# megaRF-mini-2_4_1.net
KiCad netlist of a schematic drawn in EAGLE
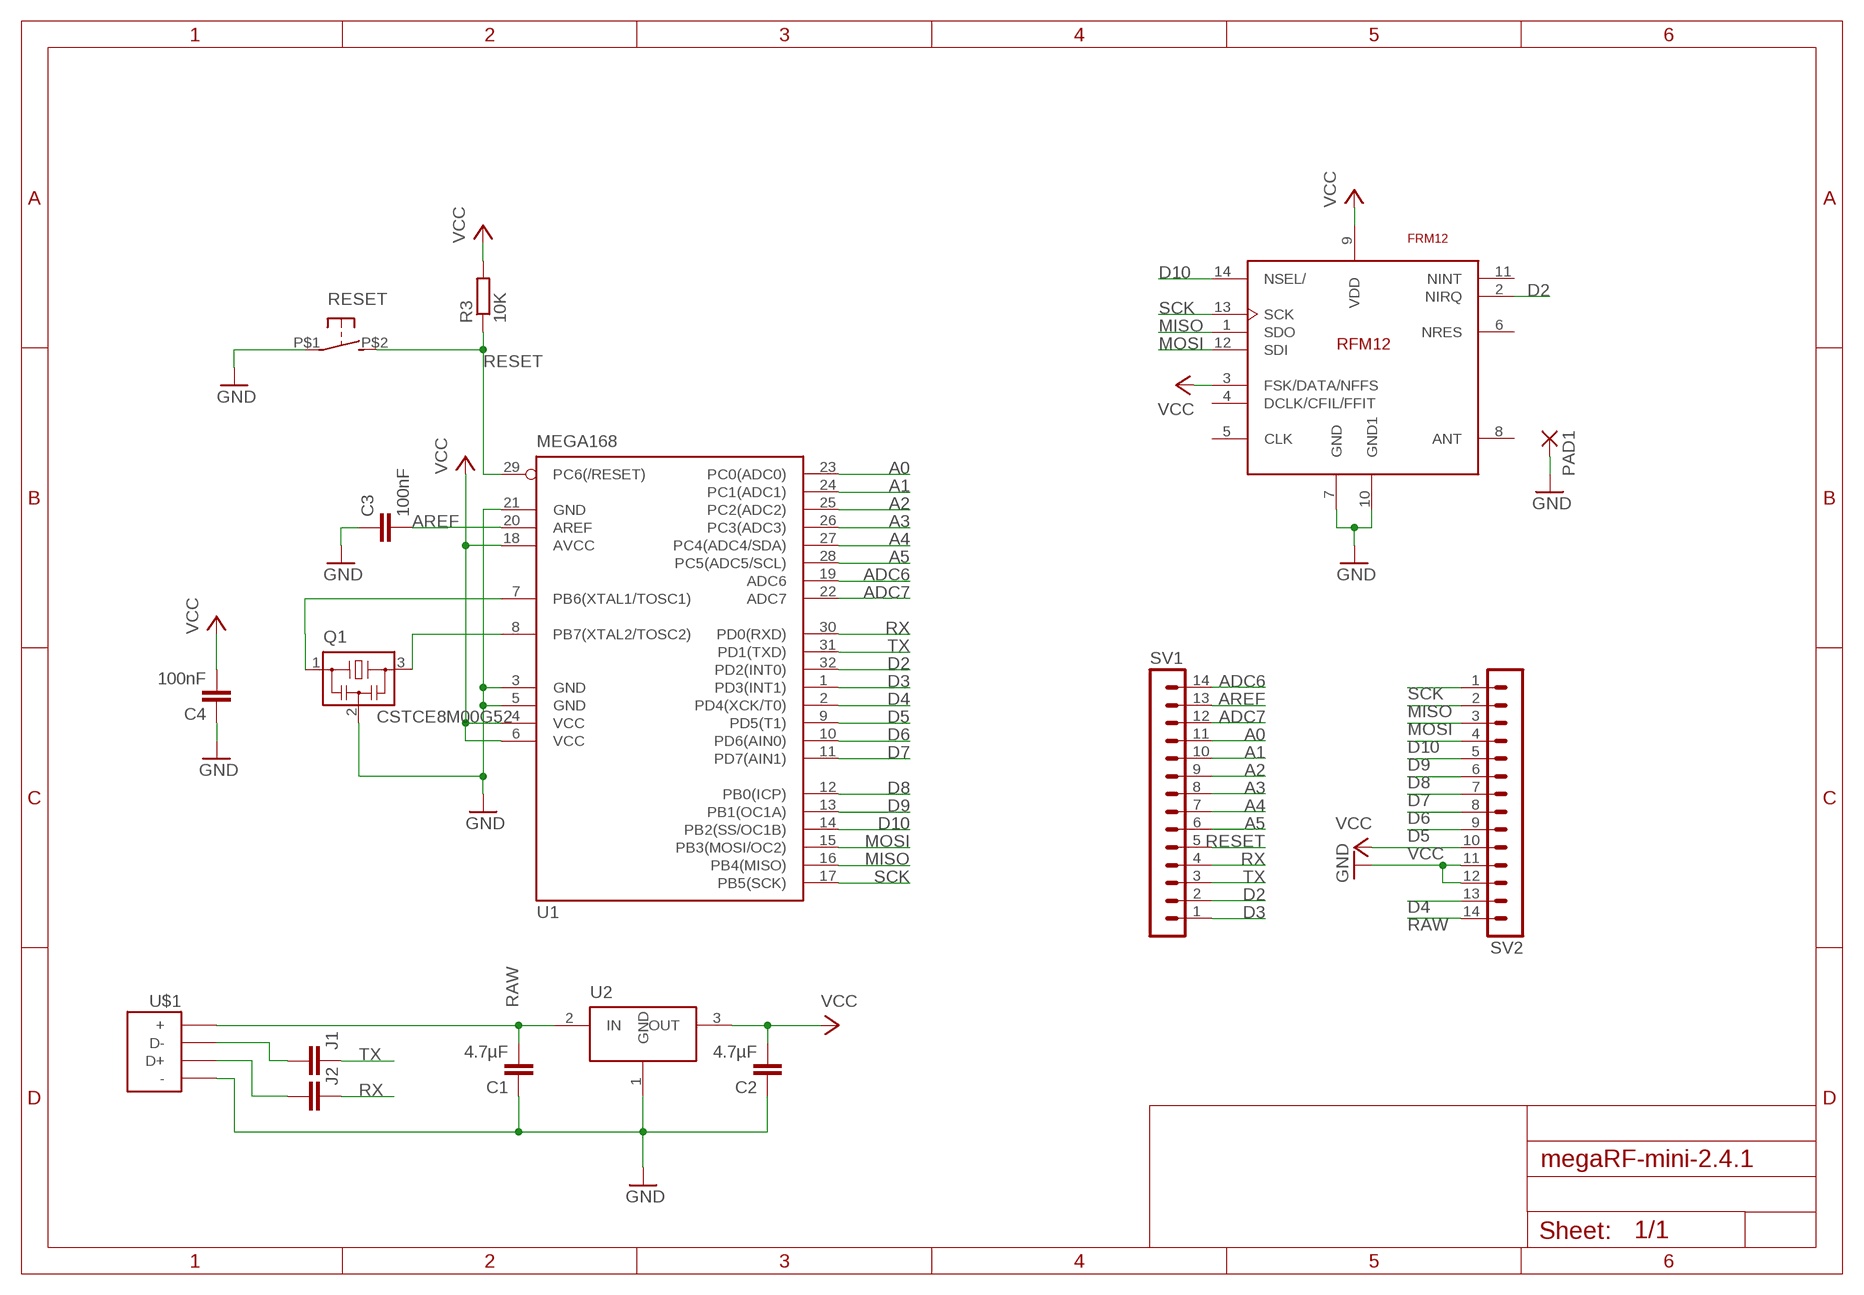
[diagram p0: schematic, sheet 1]

(export (version "E")
  (design (tool "Eeschema 10.0.6"))
  (components
    (comp (ref "C1")
      (value "4.7µF")
      (footprint "eagle-import:C0805")
      (libsource (lib "eagle-import") (part "C-EUC0805"))
    )
    (comp (ref "C2")
      (value "4.7µF")
      (footprint "eagle-import:C0805")
      (libsource (lib "eagle-import") (part "C-EUC0805"))
    )
    (comp (ref "C3")
      (value "100nF")
      (footprint "eagle-import:C0603K")
      (libsource (lib "eagle-import") (part "C-EUC0603K"))
    )
    (comp (ref "C4")
      (value "100nF")
      (footprint "eagle-import:C0603K")
      (libsource (lib "eagle-import") (part "C-EUC0603K"))
    )
    (comp (ref "J1")
      (value "C-EUC0402")
      (footprint "eagle-import:C0402")
      (libsource (lib "eagle-import") (part "C-EUC0402"))
    )
    (comp (ref "J2")
      (value "C-EUC0402")
      (footprint "eagle-import:C0402")
      (libsource (lib "eagle-import") (part "C-EUC0402"))
    )
    (comp (ref "PAD1")
      (value "SMD2")
      (footprint "eagle-import:SMD1,27-2,54")
      (libsource (lib "eagle-import") (part "SMD2"))
    )
    (comp (ref "Q1")
      (value "CSTCE8M00G52")
      (footprint "eagle-import:CSTCE8M00G52")
      (libsource (lib "eagle-import") (part "CSTCE8M00G52"))
    )
    (comp (ref "R3")
      (value "10K")
      (footprint "eagle-import:R0603")
      (libsource (lib "eagle-import") (part "R-EU_R0603"))
    )
    (comp (ref "RESET")
      (value "DTSM-3")
      (footprint "eagle-import:DTSM31N")
      (libsource (lib "eagle-import") (part "DTSM-3"))
    )
    (comp (ref "RFM12")
      (value "FRM12")
      (footprint "eagle-import:RFM12")
      (libsource (lib "eagle-import") (part "FRM12"))
    )
    (comp (ref "SV1")
      (value "MA14-1")
      (footprint "eagle-import:MA14-1")
      (libsource (lib "eagle-import") (part "MA14-1"))
    )
    (comp (ref "SV2")
      (value "MA14-1")
      (footprint "eagle-import:MA14-1")
      (libsource (lib "eagle-import") (part "MA14-1"))
    )
    (comp (ref "U$1")
      (value "USB-MICRO-B-RS")
      (footprint "eagle-import:USB-MICRO-B-RS")
      (libsource (lib "eagle-import") (part "USB-MICRO-B-RS"))
    )
    (comp (ref "U1")
      (value "MEGA168")
      (footprint "eagle-import:TQFP32-08")
      (fields (field (name "MPN") "ATMEGA8-16AU"))
      (libsource (lib "eagle-import") (part "MEGA8-AI"))
    )
    (comp (ref "U2")
      (value "TS1117CP33")
      (footprint "eagle-import:TO252")
      (libsource (lib "eagle-import") (part "TS1117CP33"))
    )
  )
  (nets
    (net (code "1") (name "/A0") (class "Default")
      (node (ref "SV1") (pin "11") (pinfunction "11_11") (pintype "passive"))
      (node (ref "U1") (pin "23") (pinfunction "PC0(ADC0)_23") (pintype "bidirectional"))
    )
    (net (code "2") (name "/A1") (class "Default")
      (node (ref "SV1") (pin "10") (pinfunction "10_10") (pintype "passive"))
      (node (ref "U1") (pin "24") (pinfunction "PC1(ADC1)_24") (pintype "bidirectional"))
    )
    (net (code "3") (name "/A2") (class "Default")
      (node (ref "SV1") (pin "9") (pinfunction "9_9") (pintype "passive"))
      (node (ref "U1") (pin "25") (pinfunction "PC2(ADC2)_25") (pintype "bidirectional"))
    )
    (net (code "4") (name "/A3") (class "Default")
      (node (ref "SV1") (pin "8") (pinfunction "8_8") (pintype "passive"))
      (node (ref "U1") (pin "26") (pinfunction "PC3(ADC3)_26") (pintype "bidirectional"))
    )
    (net (code "5") (name "/A4") (class "Default")
      (node (ref "SV1") (pin "7") (pinfunction "7_7") (pintype "passive"))
      (node (ref "U1") (pin "27") (pinfunction "PC4(ADC4/SDA)_27") (pintype "bidirectional"))
    )
    (net (code "6") (name "/A5") (class "Default")
      (node (ref "SV1") (pin "6") (pinfunction "6_6") (pintype "passive"))
      (node (ref "U1") (pin "28") (pinfunction "PC5(ADC5/SCL)_28") (pintype "bidirectional"))
    )
    (net (code "7") (name "/ADC6") (class "Default")
      (node (ref "SV1") (pin "14") (pinfunction "14_14") (pintype "passive"))
      (node (ref "U1") (pin "19") (pinfunction "ADC6_19") (pintype "bidirectional"))
    )
    (net (code "8") (name "/ADC7") (class "Default")
      (node (ref "SV1") (pin "12") (pinfunction "12_12") (pintype "passive"))
      (node (ref "U1") (pin "22") (pinfunction "ADC7_22") (pintype "bidirectional"))
    )
    (net (code "9") (name "/AREF") (class "Default")
      (node (ref "C3") (pin "2") (pinfunction "2_2") (pintype "passive"))
      (node (ref "SV1") (pin "13") (pinfunction "13_13") (pintype "passive"))
      (node (ref "U1") (pin "20") (pinfunction "AREF_20") (pintype "passive"))
    )
    (net (code "10") (name "/D2") (class "Default")
      (node (ref "RFM12") (pin "2") (pinfunction "NIRQ_2") (pintype "output"))
      (node (ref "SV1") (pin "2") (pinfunction "2_2") (pintype "passive"))
      (node (ref "U1") (pin "32") (pinfunction "PD2(INT0)_32") (pintype "bidirectional"))
    )
    (net (code "11") (name "/D3") (class "Default")
      (node (ref "SV1") (pin "1") (pinfunction "1_1") (pintype "passive"))
      (node (ref "U1") (pin "1") (pinfunction "PD3(INT1)_1") (pintype "bidirectional"))
    )
    (net (code "12") (name "/D4") (class "Default")
      (node (ref "SV2") (pin "13") (pinfunction "13_13") (pintype "passive"))
      (node (ref "U1") (pin "2") (pinfunction "PD4(XCK/T0)_2") (pintype "bidirectional"))
    )
    (net (code "13") (name "/D5") (class "Default")
      (node (ref "SV2") (pin "9") (pinfunction "9_9") (pintype "passive"))
      (node (ref "U1") (pin "9") (pinfunction "PD5(T1)_9") (pintype "bidirectional"))
    )
    (net (code "14") (name "/D6") (class "Default")
      (node (ref "SV2") (pin "8") (pinfunction "8_8") (pintype "passive"))
      (node (ref "U1") (pin "10") (pinfunction "PD6(AIN0)_10") (pintype "bidirectional"))
    )
    (net (code "15") (name "/D7") (class "Default")
      (node (ref "SV2") (pin "7") (pinfunction "7_7") (pintype "passive"))
      (node (ref "U1") (pin "11") (pinfunction "PD7(AIN1)_11") (pintype "bidirectional"))
    )
    (net (code "16") (name "/D8") (class "Default")
      (node (ref "SV2") (pin "6") (pinfunction "6_6") (pintype "passive"))
      (node (ref "U1") (pin "12") (pinfunction "PB0(ICP)_12") (pintype "bidirectional"))
    )
    (net (code "17") (name "/D9") (class "Default")
      (node (ref "SV2") (pin "5") (pinfunction "5_5") (pintype "passive"))
      (node (ref "U1") (pin "13") (pinfunction "PB1(OC1A)_13") (pintype "bidirectional"))
    )
    (net (code "18") (name "/D10") (class "Default")
      (node (ref "RFM12") (pin "14") (pinfunction "NSEL/_14") (pintype "input"))
      (node (ref "SV2") (pin "4") (pinfunction "4_4") (pintype "passive"))
      (node (ref "U1") (pin "14") (pinfunction "PB2(SS/OC1B)_14") (pintype "bidirectional"))
    )
    (net (code "19") (name "/MISO") (class "Default")
      (node (ref "RFM12") (pin "1") (pinfunction "SDO_1") (pintype "output"))
      (node (ref "SV2") (pin "2") (pinfunction "2_2") (pintype "passive"))
      (node (ref "U1") (pin "16") (pinfunction "PB4(MISO)_16") (pintype "bidirectional"))
    )
    (net (code "20") (name "/MOSI") (class "Default")
      (node (ref "RFM12") (pin "12") (pinfunction "SDI_12") (pintype "input"))
      (node (ref "SV2") (pin "3") (pinfunction "3_3") (pintype "passive"))
      (node (ref "U1") (pin "15") (pinfunction "PB3(MOSI/OC2)_15") (pintype "bidirectional"))
    )
    (net (code "21") (name "/RAW") (class "Default")
      (node (ref "C1") (pin "2") (pinfunction "2_2") (pintype "passive"))
      (node (ref "SV2") (pin "14") (pinfunction "14_14") (pintype "passive"))
      (node (ref "U$1") (pin "P$1") (pinfunction "+_P$1") (pintype "bidirectional"))
      (node (ref "U2") (pin "2") (pinfunction "IN_2") (pintype "bidirectional"))
    )
    (net (code "22") (name "/RESET") (class "Default")
      (node (ref "R3") (pin "1") (pinfunction "1_1") (pintype "passive"))
      (node (ref "RESET") (pin "P$2") (pinfunction "S_P$2") (pintype "passive"))
      (node (ref "SV1") (pin "5") (pinfunction "5_5") (pintype "passive"))
      (node (ref "U1") (pin "29") (pinfunction "PC6(/RESET)_29") (pintype "bidirectional"))
    )
    (net (code "23") (name "/RX") (class "Default")
      (node (ref "J2") (pin "2") (pinfunction "2_2") (pintype "passive"))
      (node (ref "SV1") (pin "4") (pinfunction "4_4") (pintype "passive"))
      (node (ref "U1") (pin "30") (pinfunction "PD0(RXD)_30") (pintype "bidirectional"))
    )
    (net (code "24") (name "/SCK") (class "Default")
      (node (ref "RFM12") (pin "13") (pinfunction "SCK_13") (pintype "input"))
      (node (ref "SV2") (pin "1") (pinfunction "1_1") (pintype "passive"))
      (node (ref "U1") (pin "17") (pinfunction "PB5(SCK)_17") (pintype "bidirectional"))
    )
    (net (code "25") (name "/TX") (class "Default")
      (node (ref "J1") (pin "1") (pinfunction "1_1") (pintype "passive"))
      (node (ref "SV1") (pin "3") (pinfunction "3_3") (pintype "passive"))
      (node (ref "U1") (pin "31") (pinfunction "PD1(TXD)_31") (pintype "bidirectional"))
    )
    (net (code "26") (name "GND") (class "Default")
      (node (ref "C1") (pin "1") (pinfunction "1_1") (pintype "passive"))
      (node (ref "C2") (pin "1") (pinfunction "1_1") (pintype "passive"))
      (node (ref "C3") (pin "1") (pinfunction "1_1") (pintype "passive"))
      (node (ref "C4") (pin "1") (pinfunction "1_1") (pintype "passive"))
      (node (ref "PAD1") (pin "1") (pinfunction "P_1") (pintype "passive"))
      (node (ref "Q1") (pin "2") (pinfunction "2_2") (pintype "passive"))
      (node (ref "RESET") (pin "P$1") (pinfunction "P_P$1") (pintype "passive"))
      (node (ref "RFM12") (pin "10") (pinfunction "GND1_10") (pintype "passive"))
      (node (ref "RFM12") (pin "7") (pinfunction "GND_7") (pintype "passive"))
      (node (ref "SV2") (pin "11") (pinfunction "11_11") (pintype "passive"))
      (node (ref "SV2") (pin "12") (pinfunction "12_12") (pintype "passive"))
      (node (ref "U$1") (pin "P$5") (pinfunction "-_P$5") (pintype "bidirectional"))
      (node (ref "U1") (pin "21") (pinfunction "GND_21") (pintype "power_in"))
      (node (ref "U1") (pin "3") (pinfunction "GND_3") (pintype "power_in"))
      (node (ref "U1") (pin "5") (pinfunction "GND_5") (pintype "power_in"))
      (node (ref "U2") (pin "1") (pinfunction "GND_1") (pintype "bidirectional"))
    )
    (net (code "27") (name "Net-(U$1-D+)") (class "Default")
      (node (ref "J2") (pin "1") (pinfunction "1_1") (pintype "passive"))
      (node (ref "U$1") (pin "P$3") (pinfunction "D+_P$3") (pintype "bidirectional"))
    )
    (net (code "28") (name "Net-(U$1-D-)") (class "Default")
      (node (ref "J1") (pin "2") (pinfunction "2_2") (pintype "passive"))
      (node (ref "U$1") (pin "P$2") (pinfunction "D-_P$2") (pintype "bidirectional"))
    )
    (net (code "29") (name "Net-(U1-PB6(XTAL1{slash}TOSC1))") (class "Default")
      (node (ref "Q1") (pin "1") (pinfunction "1_1") (pintype "passive"))
      (node (ref "U1") (pin "7") (pinfunction "PB6(XTAL1/TOSC1)_7") (pintype "bidirectional"))
    )
    (net (code "30") (name "Net-(U1-PB7(XTAL2{slash}TOSC2))") (class "Default")
      (node (ref "Q1") (pin "3") (pinfunction "3_3") (pintype "passive"))
      (node (ref "U1") (pin "8") (pinfunction "PB7(XTAL2/TOSC2)_8") (pintype "bidirectional"))
    )
    (net (code "31") (name "VCC") (class "Default")
      (node (ref "C2") (pin "2") (pinfunction "2_2") (pintype "passive"))
      (node (ref "C4") (pin "2") (pinfunction "2_2") (pintype "passive"))
      (node (ref "R3") (pin "2") (pinfunction "2_2") (pintype "passive"))
      (node (ref "RFM12") (pin "3") (pinfunction "FSK/DATA/NFFS_3") (pintype "bidirectional"))
      (node (ref "RFM12") (pin "9") (pinfunction "VDD_9") (pintype "power_in"))
      (node (ref "SV2") (pin "10") (pinfunction "10_10") (pintype "passive"))
      (node (ref "U1") (pin "18") (pinfunction "AVCC_18") (pintype "power_in"))
      (node (ref "U1") (pin "4") (pinfunction "VCC_4") (pintype "power_in"))
      (node (ref "U1") (pin "6") (pinfunction "VCC_6") (pintype "power_in"))
      (node (ref "U2") (pin "3") (pinfunction "OUT_3") (pintype "bidirectional"))
    )
    (net (code "32") (name "unconnected-(RFM12-ANT-Pad8)") (class "Default")
      (node (ref "RFM12") (pin "8") (pinfunction "ANT_8") (pintype "bidirectional"))
    )
    (net (code "33") (name "unconnected-(RFM12-CLK-Pad5)") (class "Default")
      (node (ref "RFM12") (pin "5") (pinfunction "CLK_5") (pintype "output"))
    )
    (net (code "34") (name "unconnected-(RFM12-DCLK{slash}CFIL{slash}FFIT-Pad4)") (class "Default")
      (node (ref "RFM12") (pin "4") (pinfunction "DCLK/CFIL/FFIT_4") (pintype "bidirectional"))
    )
    (net (code "35") (name "unconnected-(RFM12-NINT-Pad11)") (class "Default")
      (node (ref "RFM12") (pin "11") (pinfunction "NINT_11") (pintype "bidirectional"))
    )
    (net (code "36") (name "unconnected-(RFM12-NRES-Pad6)") (class "Default")
      (node (ref "RFM12") (pin "6") (pinfunction "NRES_6") (pintype "bidirectional"))
    )
  )
)
